# displays.net
KiCad netlist of a schematic drawn in Altium Designer
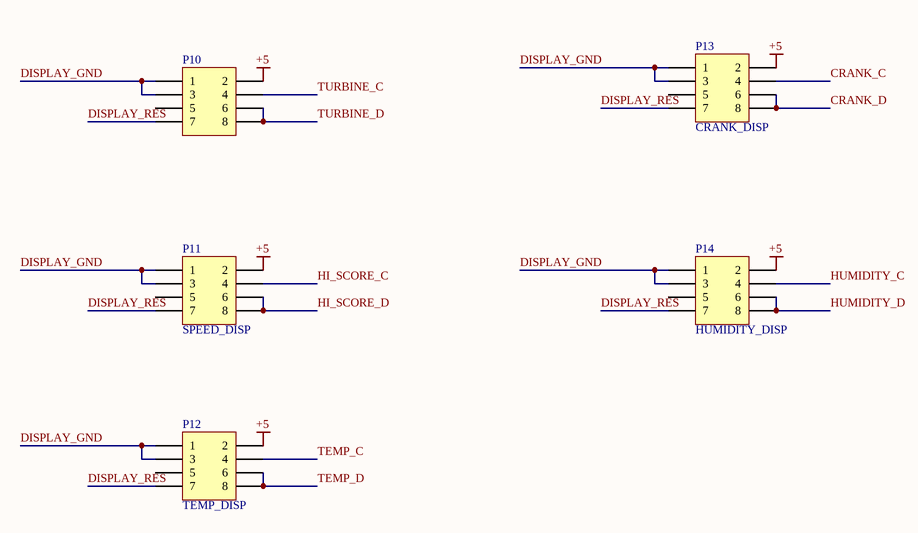
[diagram p0: displays.SchDoc]

(export (version "E")
  (design (tool "Eeschema 10.0.6"))
  (components
    (comp (ref "P10")
      (value "~")
      (footprint "HDR2X4")
      (description "Header, 4-Pin, Dual row")
      (fields (field (name "PUBLISHER") "Altium Limited"))
      (libsource (lib "Miscellaneous Connectors") (part "Header 4X2"))
    )
    (comp (ref "P11")
      (value "SPEED_DISP")
      (footprint "HDR2X4")
      (description "Header, 4-Pin, Dual row")
      (fields (field (name "PUBLISHER") "Altium Limited"))
      (libsource (lib "Miscellaneous Connectors") (part "Header 4X2"))
    )
    (comp (ref "P12")
      (value "TEMP_DISP")
      (footprint "HDR2X4")
      (description "Header, 4-Pin, Dual row")
      (fields (field (name "PUBLISHER") "Altium Limited"))
      (libsource (lib "Miscellaneous Connectors") (part "Header 4X2"))
    )
    (comp (ref "P13")
      (value "CRANK_DISP")
      (footprint "HDR2X4")
      (description "Header, 4-Pin, Dual row")
      (fields (field (name "PUBLISHER") "Altium Limited"))
      (libsource (lib "Miscellaneous Connectors") (part "Header 4X2"))
    )
    (comp (ref "P14")
      (value "HUMIDITY_DISP")
      (footprint "HDR2X4")
      (description "Header, 4-Pin, Dual row")
      (fields (field (name "PUBLISHER") "Altium Limited"))
      (libsource (lib "Miscellaneous Connectors") (part "Header 4X2"))
    )
  )
  (nets
    (net (code "1") (name "+5") (class "Default")
      (node (ref "P10") (pin "2") (pinfunction "2_2") (pintype "passive"))
      (node (ref "P11") (pin "2") (pinfunction "2_2") (pintype "passive"))
      (node (ref "P12") (pin "2") (pinfunction "2_2") (pintype "passive"))
      (node (ref "P13") (pin "2") (pinfunction "2_2") (pintype "passive"))
      (node (ref "P14") (pin "2") (pinfunction "2_2") (pintype "passive"))
    )
    (net (code "2") (name "/CRANK_C") (class "Default")
      (node (ref "P13") (pin "4") (pinfunction "4_4") (pintype "passive"))
    )
    (net (code "3") (name "/CRANK_D") (class "Default")
      (node (ref "P13") (pin "6") (pinfunction "6_6") (pintype "passive"))
      (node (ref "P13") (pin "8") (pinfunction "8_8") (pintype "passive"))
    )
    (net (code "4") (name "/DISPLAY_GND") (class "Default")
      (node (ref "P10") (pin "1") (pinfunction "1_1") (pintype "passive"))
      (node (ref "P10") (pin "3") (pinfunction "3_3") (pintype "passive"))
      (node (ref "P11") (pin "1") (pinfunction "1_1") (pintype "passive"))
      (node (ref "P11") (pin "3") (pinfunction "3_3") (pintype "passive"))
      (node (ref "P12") (pin "1") (pinfunction "1_1") (pintype "passive"))
      (node (ref "P12") (pin "3") (pinfunction "3_3") (pintype "passive"))
      (node (ref "P13") (pin "1") (pinfunction "1_1") (pintype "passive"))
      (node (ref "P13") (pin "3") (pinfunction "3_3") (pintype "passive"))
      (node (ref "P14") (pin "1") (pinfunction "1_1") (pintype "passive"))
      (node (ref "P14") (pin "3") (pinfunction "3_3") (pintype "passive"))
    )
    (net (code "5") (name "/DISPLAY_RES") (class "Default")
      (node (ref "P10") (pin "7") (pinfunction "7_7") (pintype "passive"))
      (node (ref "P11") (pin "7") (pinfunction "7_7") (pintype "passive"))
      (node (ref "P12") (pin "7") (pinfunction "7_7") (pintype "passive"))
      (node (ref "P13") (pin "7") (pinfunction "7_7") (pintype "passive"))
      (node (ref "P14") (pin "7") (pinfunction "7_7") (pintype "passive"))
    )
    (net (code "6") (name "/HI_SCORE_C") (class "Default")
      (node (ref "P11") (pin "4") (pinfunction "4_4") (pintype "passive"))
    )
    (net (code "7") (name "/HI_SCORE_D") (class "Default")
      (node (ref "P11") (pin "6") (pinfunction "6_6") (pintype "passive"))
      (node (ref "P11") (pin "8") (pinfunction "8_8") (pintype "passive"))
    )
    (net (code "8") (name "/HUMIDITY_C") (class "Default")
      (node (ref "P14") (pin "4") (pinfunction "4_4") (pintype "passive"))
    )
    (net (code "9") (name "/HUMIDITY_D") (class "Default")
      (node (ref "P14") (pin "6") (pinfunction "6_6") (pintype "passive"))
      (node (ref "P14") (pin "8") (pinfunction "8_8") (pintype "passive"))
    )
    (net (code "10") (name "/TEMP_C") (class "Default")
      (node (ref "P12") (pin "4") (pinfunction "4_4") (pintype "passive"))
    )
    (net (code "11") (name "/TEMP_D") (class "Default")
      (node (ref "P12") (pin "6") (pinfunction "6_6") (pintype "passive"))
      (node (ref "P12") (pin "8") (pinfunction "8_8") (pintype "passive"))
    )
    (net (code "12") (name "/TURBINE_C") (class "Default")
      (node (ref "P10") (pin "4") (pinfunction "4_4") (pintype "passive"))
    )
    (net (code "13") (name "/TURBINE_D") (class "Default")
      (node (ref "P10") (pin "6") (pinfunction "6_6") (pintype "passive"))
      (node (ref "P10") (pin "8") (pinfunction "8_8") (pintype "passive"))
    )
    (net (code "14") (name "unconnected-(P10-Pad5)") (class "Default")
      (node (ref "P10") (pin "5") (pinfunction "5_5") (pintype "passive"))
    )
    (net (code "15") (name "unconnected-(P11-Pad5)") (class "Default")
      (node (ref "P11") (pin "5") (pinfunction "5_5") (pintype "passive"))
    )
    (net (code "16") (name "unconnected-(P12-Pad5)") (class "Default")
      (node (ref "P12") (pin "5") (pinfunction "5_5") (pintype "passive"))
    )
    (net (code "17") (name "unconnected-(P13-Pad5)") (class "Default")
      (node (ref "P13") (pin "5") (pinfunction "5_5") (pintype "passive"))
    )
    (net (code "18") (name "unconnected-(P14-Pad5)") (class "Default")
      (node (ref "P14") (pin "5") (pinfunction "5_5") (pintype "passive"))
    )
  )
)
